# Power.net
KiCad netlist of a schematic drawn in Altium Designer
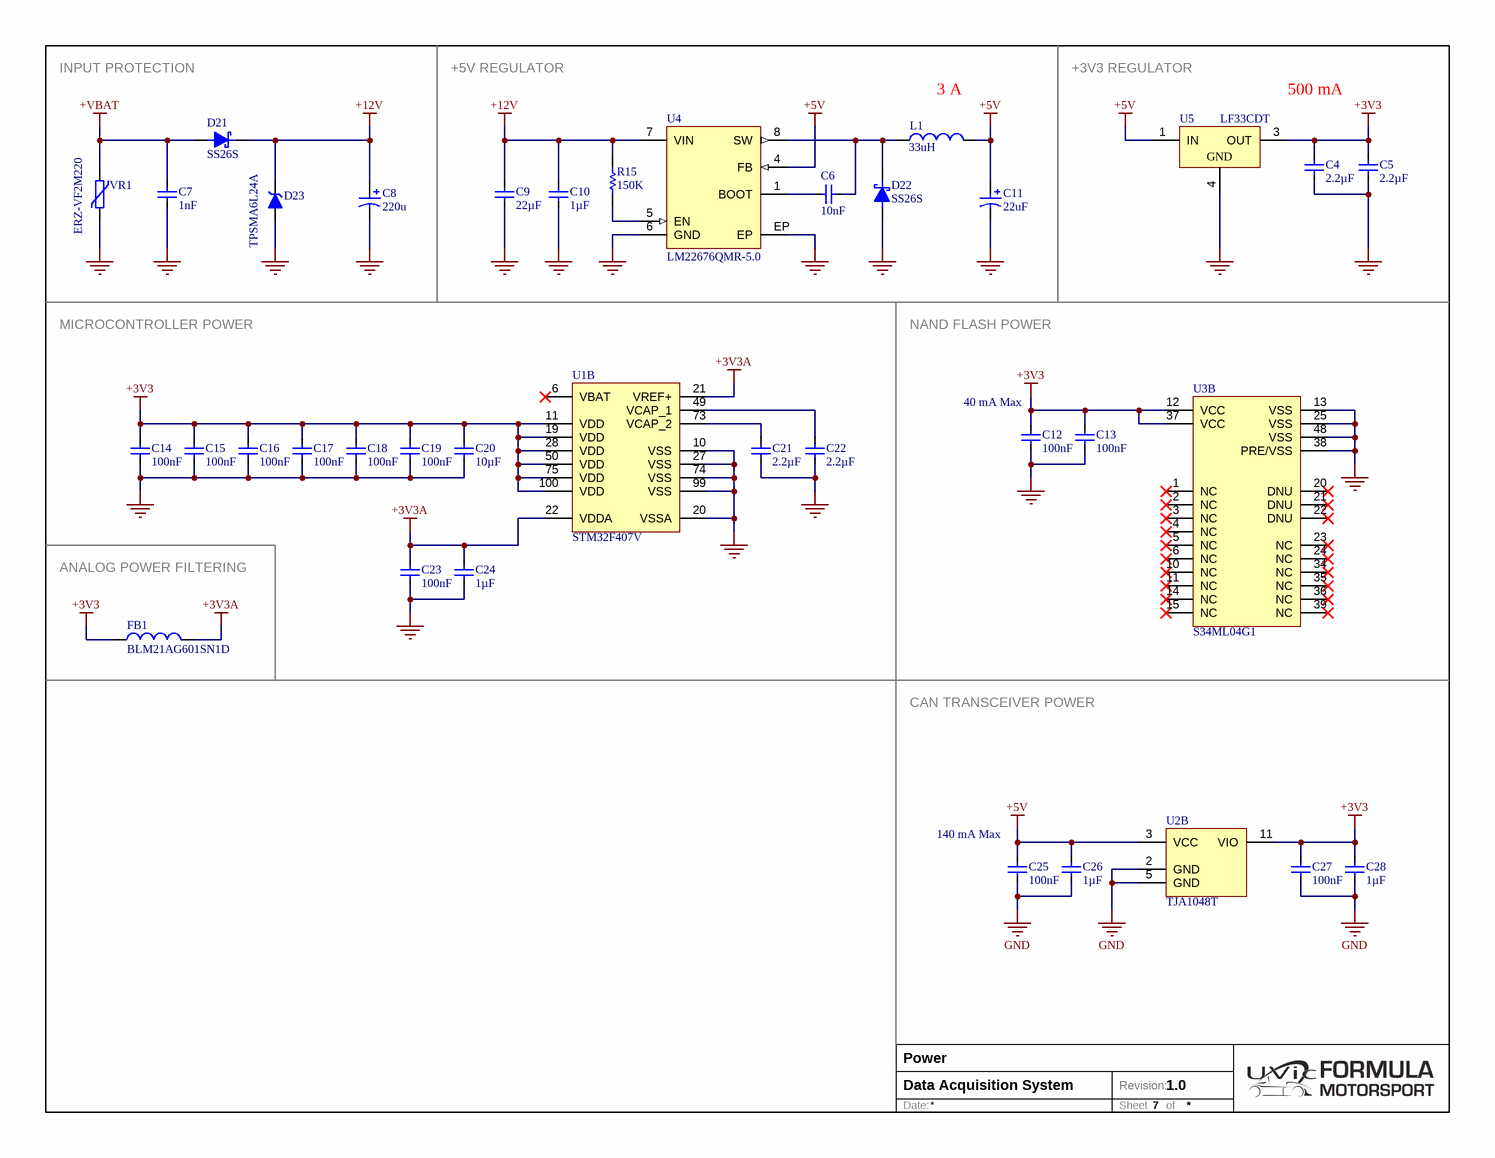
[diagram p0: Power.SchDoc]

(export (version "E")
  (design (tool "Eeschema 10.0.6"))
  (components
    (comp (ref "C4")
      (value "2.2µF")
      (footprint "CAP-0805-M")
      (fields
        (field (name "PART NUMBER") "CC0805KKX7R6BB225")
        (field (name "TOLERANCE") "±10%")
        (field (name "VOLTAGE") "10V")
      )
      (libsource (lib "Capacitors") (part "Capacitor"))
    )
    (comp (ref "C5")
      (value "2.2µF")
      (footprint "CAP-0805-M")
      (fields
        (field (name "PART NUMBER") "CC0805KKX7R6BB225")
        (field (name "TOLERANCE") "±10%")
        (field (name "VOLTAGE") "10V")
      )
      (libsource (lib "Capacitors") (part "Capacitor"))
    )
    (comp (ref "C6")
      (value "10nF")
      (footprint "CAP-0603-M")
      (fields
        (field (name "PART NUMBER") "CC0603KRX7R9BB103")
        (field (name "TOLERANCE") "±10%")
        (field (name "VOLTAGE") "50V")
      )
      (libsource (lib "Capacitors") (part "Capacitor"))
    )
    (comp (ref "C7")
      (value "1nF")
      (footprint "CAP-0805-M")
      (fields
        (field (name "PART NUMBER") "CC0805KRX7R9BB102")
        (field (name "TOLERANCE") "±10%")
        (field (name "VOLTAGE") "50V")
      )
      (libsource (lib "Capacitors") (part "Capacitor"))
    )
    (comp (ref "C8")
      (value "220u")
      (footprint "CAPAE9083X70M")
      (description "SMD Polymer Electrolytic Capacitor")
      (fields (field (name "Comment") "PCR1E221MCL1GS"))
      (libsource (lib "DAQ") (part "PCR1E221MCL1GS"))
    )
    (comp (ref "C9")
      (value "22µF")
      (footprint "CAP-1210-M")
      (fields
        (field (name "PART NUMBER") "CC1210KKX7R8BB226")
        (field (name "TOLERANCE") "±10%")
        (field (name "VOLTAGE") "25V")
      )
      (libsource (lib "Capacitors") (part "Capacitor"))
    )
    (comp (ref "C10")
      (value "1µF")
      (footprint "CAP-0805-M")
      (fields
        (field (name "PART NUMBER") "CC0805KKX7R7BB105")
        (field (name "TOLERANCE") "±10%")
        (field (name "VOLTAGE") "16V")
      )
      (libsource (lib "Capacitors") (part "Capacitor"))
    )
    (comp (ref "C11")
      (value "22uF")
      (footprint "CAP-B1")
      (description "CAP TANT 22UF 8V 20% B1")
      (fields (field (name "Comment") "8TPC22M"))
      (libsource (lib "DAQ") (part "8TPC22M"))
    )
    (comp (ref "C12")
      (value "100nF")
      (footprint "CAP-0603-M")
      (fields
        (field (name "PART NUMBER") "CC0603KRX7R8BB104")
        (field (name "TOLERANCE") "±10%")
        (field (name "VOLTAGE") "25V")
      )
      (libsource (lib "Capacitors") (part "Capacitor"))
    )
    (comp (ref "C13")
      (value "100nF")
      (footprint "CAP-0603-M")
      (fields
        (field (name "PART NUMBER") "CC0603KRX7R8BB104")
        (field (name "TOLERANCE") "±10%")
        (field (name "VOLTAGE") "25V")
      )
      (libsource (lib "Capacitors") (part "Capacitor"))
    )
    (comp (ref "C14")
      (value "100nF")
      (footprint "CAP-0603-M")
      (fields
        (field (name "PART NUMBER") "CC0603KRX7R8BB104")
        (field (name "TOLERANCE") "±10%")
        (field (name "VOLTAGE") "25V")
      )
      (libsource (lib "Capacitors") (part "Capacitor"))
    )
    (comp (ref "C15")
      (value "100nF")
      (footprint "CAP-0603-M")
      (fields
        (field (name "PART NUMBER") "CC0603KRX7R8BB104")
        (field (name "TOLERANCE") "±10%")
        (field (name "VOLTAGE") "25V")
      )
      (libsource (lib "Capacitors") (part "Capacitor"))
    )
    (comp (ref "C16")
      (value "100nF")
      (footprint "CAP-0603-M")
      (fields
        (field (name "PART NUMBER") "CC0603KRX7R8BB104")
        (field (name "TOLERANCE") "±10%")
        (field (name "VOLTAGE") "25V")
      )
      (libsource (lib "Capacitors") (part "Capacitor"))
    )
    (comp (ref "C17")
      (value "100nF")
      (footprint "CAP-0603-M")
      (fields
        (field (name "PART NUMBER") "CC0603KRX7R8BB104")
        (field (name "TOLERANCE") "±10%")
        (field (name "VOLTAGE") "25V")
      )
      (libsource (lib "Capacitors") (part "Capacitor"))
    )
    (comp (ref "C18")
      (value "100nF")
      (footprint "CAP-0603-M")
      (fields
        (field (name "PART NUMBER") "CC0603KRX7R8BB104")
        (field (name "TOLERANCE") "±10%")
        (field (name "VOLTAGE") "25V")
      )
      (libsource (lib "Capacitors") (part "Capacitor"))
    )
    (comp (ref "C19")
      (value "100nF")
      (footprint "CAP-0603-M")
      (fields
        (field (name "PART NUMBER") "CC0603KRX7R8BB104")
        (field (name "TOLERANCE") "±10%")
        (field (name "VOLTAGE") "25V")
      )
      (libsource (lib "Capacitors") (part "Capacitor"))
    )
    (comp (ref "C20")
      (value "10µF")
      (footprint "CAP-0805-M")
      (fields
        (field (name "PART NUMBER") "CC0805KKX5R6BB106")
        (field (name "TOLERANCE") "±10%")
        (field (name "VOLTAGE") "10V")
      )
      (libsource (lib "Capacitors") (part "Capacitor"))
    )
    (comp (ref "C21")
      (value "2.2µF")
      (footprint "CAP-0805-M")
      (fields
        (field (name "PART NUMBER") "CC0805KKX7R6BB225")
        (field (name "TOLERANCE") "±10%")
        (field (name "VOLTAGE") "10V")
      )
      (libsource (lib "Capacitors") (part "Capacitor"))
    )
    (comp (ref "C22")
      (value "2.2µF")
      (footprint "CAP-0805-M")
      (fields
        (field (name "PART NUMBER") "CC0805KKX7R6BB225")
        (field (name "TOLERANCE") "±10%")
        (field (name "VOLTAGE") "10V")
      )
      (libsource (lib "Capacitors") (part "Capacitor"))
    )
    (comp (ref "C23")
      (value "100nF")
      (footprint "CAP-0603-M")
      (fields
        (field (name "PART NUMBER") "CC0603KRX7R8BB104")
        (field (name "TOLERANCE") "±10%")
        (field (name "VOLTAGE") "25V")
      )
      (libsource (lib "Capacitors") (part "Capacitor"))
    )
    (comp (ref "C24")
      (value "1µF")
      (footprint "CAP-0805-M")
      (fields
        (field (name "PART NUMBER") "CC0805KKX7R7BB105")
        (field (name "TOLERANCE") "±10%")
        (field (name "VOLTAGE") "16V")
      )
      (libsource (lib "Capacitors") (part "Capacitor"))
    )
    (comp (ref "C25")
      (value "100nF")
      (footprint "CAP-0603-M")
      (fields
        (field (name "PART NUMBER") "CC0603KRX7R8BB104")
        (field (name "TOLERANCE") "±10%")
        (field (name "VOLTAGE") "25V")
      )
      (libsource (lib "Capacitors") (part "Capacitor"))
    )
    (comp (ref "C26")
      (value "1µF")
      (footprint "CAP-0805-M")
      (fields
        (field (name "PART NUMBER") "CC0805KKX7R7BB105")
        (field (name "TOLERANCE") "±10%")
        (field (name "VOLTAGE") "16V")
      )
      (libsource (lib "Capacitors") (part "Capacitor"))
    )
    (comp (ref "C27")
      (value "100nF")
      (footprint "CAP-0603-M")
      (fields
        (field (name "PART NUMBER") "CC0603KRX7R8BB104")
        (field (name "TOLERANCE") "±10%")
        (field (name "VOLTAGE") "25V")
      )
      (libsource (lib "Capacitors") (part "Capacitor"))
    )
    (comp (ref "C28")
      (value "1µF")
      (footprint "CAP-0805-M")
      (fields
        (field (name "PART NUMBER") "CC0805KKX7R7BB105")
        (field (name "TOLERANCE") "±10%")
        (field (name "VOLTAGE") "16V")
      )
      (libsource (lib "Capacitors") (part "Capacitor"))
    )
    (comp (ref "D21")
      (value "SS26S")
      (footprint "DO-214AC (SMA)")
      (description "SMD Schottky Diode")
      (libsource (lib "DAQ") (part "SS26S"))
    )
    (comp (ref "D22")
      (value "SS26S")
      (footprint "DO-214AC (SMA)")
      (description "SMD Schottky Diode")
      (libsource (lib "DAQ") (part "SS26S"))
    )
    (comp (ref "D23")
      (value "TPSMA6L24A")
      (footprint "SODFL520X110-2N")
      (description "SMD TVS Diode")
      (libsource (lib "DAQ") (part "TPSMA6L24A"))
    )
    (comp (ref "FB1")
      (value "BLM21AG601SN1D")
      (footprint "MURA-BLM21A")
      (description "Chip Ferrite Bead (0805) 600R at 100MHz")
      (libsource (lib "DAQ") (part "BLM21AG601SN1D"))
    )
    (comp (ref "L1")
      (value "33uH")
      (footprint "INDP125125X65N")
      (description "SRR1260 Shield SMD Power Inductor")
      (fields (field (name "Comment") "SRR1260A-330M"))
      (libsource (lib "DAQ") (part "SRR1260A-330M"))
    )
    (comp (ref "R15")
      (value "150K")
      (footprint "RES-0603-M")
      (fields
        (field (name "PART NUMBER") "RC0603FR-07150KL")
        (field (name "TOLERANCE") "1%")
        (field (name "POWER") "1/10 W")
      )
      (libsource (lib "Resistors") (part "Resistor"))
    )
    (comp (ref "U1")
      (value "STM32F407V")
      (footprint "100-LQFP-14x14-0.5")
      (description "STM32F407 100-LQFP")
      (libsource (lib "DAQ") (part "STM32F407V"))
    )
    (comp (ref "U2")
      (value "TJA1048T")
      (footprint "SOP127P600X175-14N")
      (description "Dual CAN transceiver")
      (libsource (lib "DAQ") (part "TJA1048T"))
    )
    (comp (ref "U3") (value "S34ML04G1") (footprint "48-TSOP") (libsource (lib "DAQ") (part "S34ML04G1")))
    (comp (ref "U4")
      (value "LM22676QMR-5.0")
      (footprint "8-SOIC-EP-4.9x3.9mm")
      (libsource (lib "DAQ") (part "LM22676QMR-5.0"))
    )
    (comp (ref "U5")
      (value "LF33CDT")
      (footprint "TO-252_M")
      (description "LDO Fixed 3.3 Automotive")
      (libsource (lib "DAQ") (part "LF33CDT"))
    )
    (comp (ref "VR1")
      (value "ERZ-VF2M220")
      (footprint "ERZ-VF")
      (description "SMD Varistor 22V")
      (libsource (lib "DAQ") (part "ERZ-VF2M220"))
    )
  )
  (nets
    (net (code "1") (name "+3V3") (class "Default")
      (node (ref "C12") (pin "1") (pinfunction "1_1") (pintype "passive"))
      (node (ref "C13") (pin "1") (pinfunction "1_1") (pintype "passive"))
      (node (ref "C14") (pin "1") (pinfunction "1_1") (pintype "passive"))
      (node (ref "C15") (pin "1") (pinfunction "1_1") (pintype "passive"))
      (node (ref "C16") (pin "1") (pinfunction "1_1") (pintype "passive"))
      (node (ref "C17") (pin "1") (pinfunction "1_1") (pintype "passive"))
      (node (ref "C18") (pin "1") (pinfunction "1_1") (pintype "passive"))
      (node (ref "C19") (pin "1") (pinfunction "1_1") (pintype "passive"))
      (node (ref "C20") (pin "1") (pinfunction "1_1") (pintype "passive"))
      (node (ref "C27") (pin "1") (pinfunction "1_1") (pintype "passive"))
      (node (ref "C28") (pin "2") (pinfunction "2_2") (pintype "passive"))
      (node (ref "C4") (pin "2") (pinfunction "2_2") (pintype "passive"))
      (node (ref "C5") (pin "2") (pinfunction "2_2") (pintype "passive"))
      (node (ref "FB1") (pin "1") (pinfunction "1_1") (pintype "passive"))
      (node (ref "U1") (pin "100") (pinfunction "VDD_100") (pintype "power_in"))
      (node (ref "U1") (pin "11") (pinfunction "VDD_11") (pintype "power_in"))
      (node (ref "U1") (pin "19") (pinfunction "VDD_19") (pintype "power_in"))
      (node (ref "U1") (pin "28") (pinfunction "VDD_28") (pintype "power_in"))
      (node (ref "U1") (pin "50") (pinfunction "VDD_50") (pintype "power_in"))
      (node (ref "U1") (pin "75") (pinfunction "VDD_75") (pintype "power_in"))
      (node (ref "U2") (pin "11") (pinfunction "VIO_11") (pintype "passive"))
      (node (ref "U3") (pin "12") (pinfunction "VCC_12") (pintype "power_in"))
      (node (ref "U3") (pin "37") (pinfunction "VCC_37") (pintype "power_in"))
      (node (ref "U5") (pin "3") (pinfunction "OUT_3") (pintype "power_in"))
    )
    (net (code "2") (name "+3V3A") (class "Default")
      (node (ref "C23") (pin "1") (pinfunction "1_1") (pintype "passive"))
      (node (ref "C24") (pin "2") (pinfunction "2_2") (pintype "passive"))
      (node (ref "FB1") (pin "2") (pinfunction "2_2") (pintype "passive"))
      (node (ref "U1") (pin "21") (pinfunction "VREF+_21") (pintype "power_in"))
      (node (ref "U1") (pin "22") (pinfunction "VDDA_22") (pintype "power_in"))
    )
    (net (code "3") (name "+5V") (class "Default")
      (node (ref "C11") (pin "1") (pinfunction "1_1") (pintype "passive"))
      (node (ref "C25") (pin "1") (pinfunction "1_1") (pintype "passive"))
      (node (ref "C26") (pin "2") (pinfunction "2_2") (pintype "passive"))
      (node (ref "L1") (pin "2") (pinfunction "2_2") (pintype "passive"))
      (node (ref "U2") (pin "3") (pinfunction "VCC_3") (pintype "passive"))
      (node (ref "U4") (pin "4") (pinfunction "FB_4") (pintype "input"))
      (node (ref "U5") (pin "1") (pinfunction "IN_1") (pintype "power_in"))
    )
    (net (code "4") (name "+12V") (class "Default")
      (node (ref "C10") (pin "2") (pinfunction "2_2") (pintype "passive"))
      (node (ref "C8") (pin "1") (pinfunction "1_1") (pintype "passive"))
      (node (ref "C9") (pin "2") (pinfunction "2_2") (pintype "passive"))
      (node (ref "D21") (pin "1") (pinfunction "K_1") (pintype "passive"))
      (node (ref "D23") (pin "1") (pinfunction "A_1") (pintype "passive"))
      (node (ref "R15") (pin "2") (pinfunction "2_2") (pintype "passive"))
      (node (ref "U4") (pin "7") (pinfunction "VIN_7") (pintype "power_in"))
    )
    (net (code "5") (name "+VBAT") (class "Default")
      (node (ref "C7") (pin "2") (pinfunction "2_2") (pintype "passive"))
      (node (ref "D21") (pin "2") (pinfunction "A_2") (pintype "passive"))
      (node (ref "VR1") (pin "2") (pinfunction "2_2") (pintype "passive"))
    )
    (net (code "6") (name "GND") (class "Default")
      (node (ref "C10") (pin "1") (pinfunction "1_1") (pintype "passive"))
      (node (ref "C11") (pin "2") (pinfunction "2_2") (pintype "passive"))
      (node (ref "C12") (pin "2") (pinfunction "2_2") (pintype "passive"))
      (node (ref "C13") (pin "2") (pinfunction "2_2") (pintype "passive"))
      (node (ref "C14") (pin "2") (pinfunction "2_2") (pintype "passive"))
      (node (ref "C15") (pin "2") (pinfunction "2_2") (pintype "passive"))
      (node (ref "C16") (pin "2") (pinfunction "2_2") (pintype "passive"))
      (node (ref "C17") (pin "2") (pinfunction "2_2") (pintype "passive"))
      (node (ref "C18") (pin "2") (pinfunction "2_2") (pintype "passive"))
      (node (ref "C19") (pin "2") (pinfunction "2_2") (pintype "passive"))
      (node (ref "C20") (pin "2") (pinfunction "2_2") (pintype "passive"))
      (node (ref "C21") (pin "1") (pinfunction "1_1") (pintype "passive"))
      (node (ref "C22") (pin "1") (pinfunction "1_1") (pintype "passive"))
      (node (ref "C23") (pin "2") (pinfunction "2_2") (pintype "passive"))
      (node (ref "C24") (pin "1") (pinfunction "1_1") (pintype "passive"))
      (node (ref "C25") (pin "2") (pinfunction "2_2") (pintype "passive"))
      (node (ref "C26") (pin "1") (pinfunction "1_1") (pintype "passive"))
      (node (ref "C27") (pin "2") (pinfunction "2_2") (pintype "passive"))
      (node (ref "C28") (pin "1") (pinfunction "1_1") (pintype "passive"))
      (node (ref "C4") (pin "1") (pinfunction "1_1") (pintype "passive"))
      (node (ref "C5") (pin "1") (pinfunction "1_1") (pintype "passive"))
      (node (ref "C7") (pin "1") (pinfunction "1_1") (pintype "passive"))
      (node (ref "C8") (pin "2") (pinfunction "2_2") (pintype "passive"))
      (node (ref "C9") (pin "1") (pinfunction "1_1") (pintype "passive"))
      (node (ref "D22") (pin "2") (pinfunction "A_2") (pintype "passive"))
      (node (ref "D23") (pin "2") (pinfunction "C_2") (pintype "passive"))
      (node (ref "U1") (pin "10") (pinfunction "VSS_10") (pintype "power_in"))
      (node (ref "U1") (pin "20") (pinfunction "VSSA_20") (pintype "power_in"))
      (node (ref "U1") (pin "27") (pinfunction "VSS_27") (pintype "power_in"))
      (node (ref "U1") (pin "74") (pinfunction "VSS_74") (pintype "power_in"))
      (node (ref "U1") (pin "99") (pinfunction "VSS_99") (pintype "power_in"))
      (node (ref "U2") (pin "2") (pinfunction "GND_2") (pintype "passive"))
      (node (ref "U2") (pin "5") (pinfunction "GND_5") (pintype "passive"))
      (node (ref "U3") (pin "13") (pinfunction "VSS_13") (pintype "power_in"))
      (node (ref "U3") (pin "25") (pinfunction "VSS_25") (pintype "power_in"))
      (node (ref "U3") (pin "38") (pinfunction "PRE/VSS_38") (pintype "power_in"))
      (node (ref "U3") (pin "48") (pinfunction "VSS_48") (pintype "power_in"))
      (node (ref "U4") (pin "6") (pinfunction "GND_6") (pintype "power_in"))
      (node (ref "U4") (pin "EP") (pinfunction "EP_EP") (pintype "power_in"))
      (node (ref "U5") (pin "4") (pinfunction "GND_4") (pintype "power_in"))
      (node (ref "VR1") (pin "1") (pinfunction "1_1") (pintype "passive"))
    )
    (net (code "7") (name "Net-(D22-K)") (class "Default")
      (node (ref "C6") (pin "2") (pinfunction "2_2") (pintype "passive"))
      (node (ref "D22") (pin "1") (pinfunction "K_1") (pintype "passive"))
      (node (ref "L1") (pin "1") (pinfunction "1_1") (pintype "passive"))
      (node (ref "U4") (pin "8") (pinfunction "SW_8") (pintype "output"))
    )
    (net (code "8") (name "Net-(U1B-VCAP_1)") (class "Default")
      (node (ref "C22") (pin "2") (pinfunction "2_2") (pintype "passive"))
      (node (ref "U1") (pin "49") (pinfunction "VCAP_1_49") (pintype "power_in"))
    )
    (net (code "9") (name "Net-(U1B-VCAP_2)") (class "Default")
      (node (ref "C21") (pin "2") (pinfunction "2_2") (pintype "passive"))
      (node (ref "U1") (pin "73") (pinfunction "VCAP_2_73") (pintype "power_in"))
    )
    (net (code "10") (name "Net-(U4-BOOT)") (class "Default")
      (node (ref "C6") (pin "1") (pinfunction "1_1") (pintype "passive"))
      (node (ref "U4") (pin "1") (pinfunction "BOOT_1") (pintype "passive"))
    )
    (net (code "11") (name "Net-(U4-EN)") (class "Default")
      (node (ref "R15") (pin "1") (pinfunction "1_1") (pintype "passive"))
      (node (ref "U4") (pin "5") (pinfunction "EN_5") (pintype "input"))
    )
    (net (code "12") (name "unconnected-(U1B-VBAT-Pad6)") (class "Default")
      (node (ref "U1") (pin "6") (pinfunction "VBAT_6") (pintype "power_in+no_connect"))
    )
    (net (code "13") (name "unconnected-(U3B-DNU-Pad20)") (class "Default")
      (node (ref "U3") (pin "20") (pinfunction "DNU_20") (pintype "passive+no_connect"))
    )
    (net (code "14") (name "unconnected-(U3B-DNU-Pad21)") (class "Default")
      (node (ref "U3") (pin "21") (pinfunction "DNU_21") (pintype "passive+no_connect"))
    )
    (net (code "15") (name "unconnected-(U3B-DNU-Pad22)") (class "Default")
      (node (ref "U3") (pin "22") (pinfunction "DNU_22") (pintype "passive+no_connect"))
    )
    (net (code "16") (name "unconnected-(U3B-NC-Pad1)") (class "Default")
      (node (ref "U3") (pin "1") (pinfunction "NC_1") (pintype "passive+no_connect"))
    )
    (net (code "17") (name "unconnected-(U3B-NC-Pad2)") (class "Default")
      (node (ref "U3") (pin "2") (pinfunction "NC_2") (pintype "passive+no_connect"))
    )
    (net (code "18") (name "unconnected-(U3B-NC-Pad3)") (class "Default")
      (node (ref "U3") (pin "3") (pinfunction "NC_3") (pintype "passive+no_connect"))
    )
    (net (code "19") (name "unconnected-(U3B-NC-Pad4)") (class "Default")
      (node (ref "U3") (pin "4") (pinfunction "NC_4") (pintype "passive+no_connect"))
    )
    (net (code "20") (name "unconnected-(U3B-NC-Pad5)") (class "Default")
      (node (ref "U3") (pin "5") (pinfunction "NC_5") (pintype "passive+no_connect"))
    )
    (net (code "21") (name "unconnected-(U3B-NC-Pad6)") (class "Default")
      (node (ref "U3") (pin "6") (pinfunction "NC_6") (pintype "passive+no_connect"))
    )
    (net (code "22") (name "unconnected-(U3B-NC-Pad10)") (class "Default")
      (node (ref "U3") (pin "10") (pinfunction "NC_10") (pintype "passive+no_connect"))
    )
    (net (code "23") (name "unconnected-(U3B-NC-Pad11)") (class "Default")
      (node (ref "U3") (pin "11") (pinfunction "NC_11") (pintype "passive+no_connect"))
    )
    (net (code "24") (name "unconnected-(U3B-NC-Pad14)") (class "Default")
      (node (ref "U3") (pin "14") (pinfunction "NC_14") (pintype "passive+no_connect"))
    )
    (net (code "25") (name "unconnected-(U3B-NC-Pad15)") (class "Default")
      (node (ref "U3") (pin "15") (pinfunction "NC_15") (pintype "passive+no_connect"))
    )
    (net (code "26") (name "unconnected-(U3B-NC-Pad23)") (class "Default")
      (node (ref "U3") (pin "23") (pinfunction "NC_23") (pintype "passive+no_connect"))
    )
    (net (code "27") (name "unconnected-(U3B-NC-Pad24)") (class "Default")
      (node (ref "U3") (pin "24") (pinfunction "NC_24") (pintype "passive+no_connect"))
    )
    (net (code "28") (name "unconnected-(U3B-NC-Pad34)") (class "Default")
      (node (ref "U3") (pin "34") (pinfunction "NC_34") (pintype "passive+no_connect"))
    )
    (net (code "29") (name "unconnected-(U3B-NC-Pad35)") (class "Default")
      (node (ref "U3") (pin "35") (pinfunction "NC_35") (pintype "passive+no_connect"))
    )
    (net (code "30") (name "unconnected-(U3B-NC-Pad36)") (class "Default")
      (node (ref "U3") (pin "36") (pinfunction "NC_36") (pintype "passive+no_connect"))
    )
    (net (code "31") (name "unconnected-(U3B-NC-Pad39)") (class "Default")
      (node (ref "U3") (pin "39") (pinfunction "NC_39") (pintype "passive+no_connect"))
    )
    (net (code "32") (name "unconnected-(U4-NC-Pad2)") (class "Default")
      (node (ref "U4") (pin "2") (pinfunction "NC_2") (pintype "passive"))
    )
    (net (code "33") (name "unconnected-(U4-NC-Pad3)") (class "Default")
      (node (ref "U4") (pin "3") (pinfunction "NC_3") (pintype "passive"))
    )
  )
)
